# mainboard.net
KiCad netlist of a schematic drawn in EAGLE
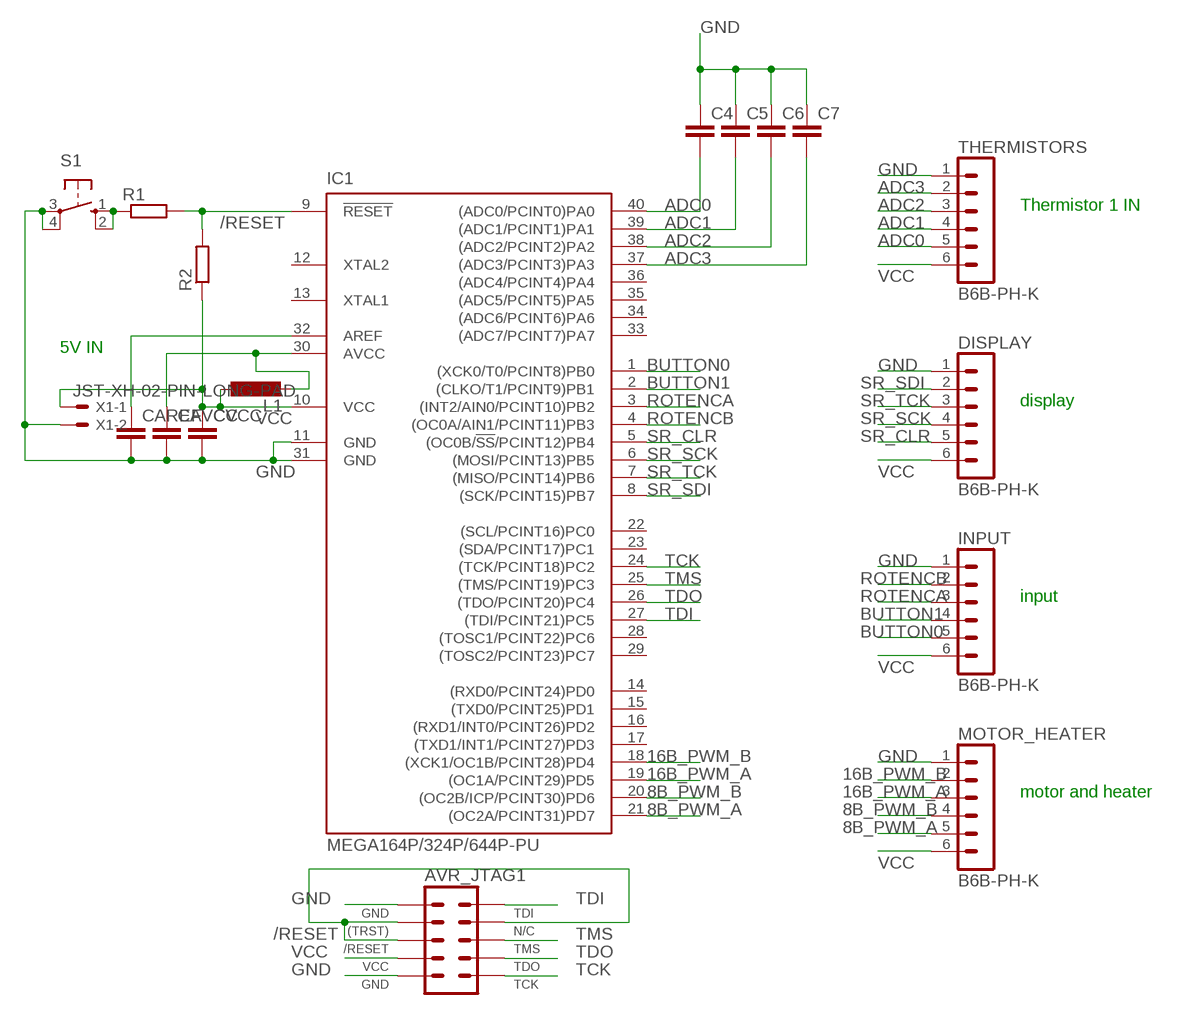
[diagram p0: schematic, sheet 1]

(export (version "E")
  (design (tool "Eeschema 10.0.6"))
  (components
    (comp (ref "AVR_JTAG1")
      (value "AVR_JTAG_2X5/IN")
      (footprint "eagle-import:AVR_JTAG_2X5")
      (libsource (lib "eagle-import") (part "AVR_JTAG_2X5/IN"))
    )
    (comp (ref "C4")
      (value "C-EU025-024X044")
      (footprint "eagle-import:C025-024X044")
      (libsource (lib "eagle-import") (part "C-EU025-024X044"))
    )
    (comp (ref "C5")
      (value "C-EU025-024X044")
      (footprint "eagle-import:C025-024X044")
      (libsource (lib "eagle-import") (part "C-EU025-024X044"))
    )
    (comp (ref "C6")
      (value "C-EU025-024X044")
      (footprint "eagle-import:C025-024X044")
      (libsource (lib "eagle-import") (part "C-EU025-024X044"))
    )
    (comp (ref "C7")
      (value "C-EU025-024X044")
      (footprint "eagle-import:C025-024X044")
      (libsource (lib "eagle-import") (part "C-EU025-024X044"))
    )
    (comp (ref "CAREF")
      (value "C-EU025-024X044")
      (footprint "eagle-import:C025-024X044")
      (libsource (lib "eagle-import") (part "C-EU025-024X044"))
    )
    (comp (ref "CAVCC")
      (value "C-EU025-024X044")
      (footprint "eagle-import:C025-024X044")
      (libsource (lib "eagle-import") (part "C-EU025-024X044"))
    )
    (comp (ref "CVCC")
      (value "C-EU025-024X044")
      (footprint "eagle-import:C025-024X044")
      (libsource (lib "eagle-import") (part "C-EU025-024X044"))
    )
    (comp (ref "DISPLAY")
      (value "B6B-PH-K")
      (footprint "eagle-import:B6B-PH-K")
      (libsource (lib "eagle-import") (part "B6B-PH-K"))
    )
    (comp (ref "IC1")
      (value "MEGA164P/324P/644P-PU")
      (footprint "eagle-import:DIL40")
      (libsource (lib "eagle-import") (part "MEGA164P/324P/644P-PU"))
    )
    (comp (ref "INPUT")
      (value "B6B-PH-K")
      (footprint "eagle-import:B6B-PH-K")
      (libsource (lib "eagle-import") (part "B6B-PH-K"))
    )
    (comp (ref "L1")
      (value "L-EU0207/10")
      (footprint "eagle-import:0207_10")
      (libsource (lib "eagle-import") (part "L-EU0207/10"))
    )
    (comp (ref "MOTOR_HEATER")
      (value "B6B-PH-K")
      (footprint "eagle-import:B6B-PH-K")
      (libsource (lib "eagle-import") (part "B6B-PH-K"))
    )
    (comp (ref "R1")
      (value "R-EU_0207/10")
      (footprint "eagle-import:0207_10")
      (libsource (lib "eagle-import") (part "R-EU_0207/10"))
    )
    (comp (ref "R2")
      (value "R-EU_0207/10")
      (footprint "eagle-import:0207_10")
      (libsource (lib "eagle-import") (part "R-EU_0207/10"))
    )
    (comp (ref "S1")
      (value "10-XX")
      (footprint "eagle-import:B3F-10XX")
      (libsource (lib "eagle-import") (part "10-XX"))
    )
    (comp (ref "THERMISTORS")
      (value "B6B-PH-K")
      (footprint "eagle-import:B6B-PH-K")
      (libsource (lib "eagle-import") (part "B6B-PH-K"))
    )
    (comp (ref "X1")
      (value "JST-XH-02-PIN-LONG-PAD")
      (footprint "eagle-import:JST-XH-02-PACKAGE-LONG-PAD")
      (libsource (lib "eagle-import") (part "JST-XH-02-PIN-LONG-PAD"))
    )
  )
  (nets
    (net (code "1") (name "/8B_PWM_A") (class "Default")
      (node (ref "IC1") (pin "21") (pinfunction "(OC2A/PCINT31)PD7_21") (pintype "bidirectional"))
      (node (ref "MOTOR_HEATER") (pin "5") (pinfunction "5_5") (pintype "passive"))
    )
    (net (code "2") (name "/8B_PWM_B") (class "Default")
      (node (ref "IC1") (pin "20") (pinfunction "(OC2B/ICP/PCINT30)PD6_20") (pintype "bidirectional"))
      (node (ref "MOTOR_HEATER") (pin "4") (pinfunction "4_4") (pintype "passive"))
    )
    (net (code "3") (name "/16B_PWM_A") (class "Default")
      (node (ref "IC1") (pin "19") (pinfunction "(OC1A/PCINT29)PD5_19") (pintype "bidirectional"))
      (node (ref "MOTOR_HEATER") (pin "3") (pinfunction "3_3") (pintype "passive"))
    )
    (net (code "4") (name "/16B_PWM_B") (class "Default")
      (node (ref "IC1") (pin "18") (pinfunction "(XCK1/OC1B/PCINT28)PD4_18") (pintype "bidirectional"))
      (node (ref "MOTOR_HEATER") (pin "2") (pinfunction "2_2") (pintype "passive"))
    )
    (net (code "5") (name "/ADC0") (class "Default")
      (node (ref "C4") (pin "2") (pinfunction "2_2") (pintype "passive"))
      (node (ref "IC1") (pin "40") (pinfunction "(ADC0/PCINT0)PA0_40") (pintype "bidirectional"))
      (node (ref "THERMISTORS") (pin "5") (pinfunction "5_5") (pintype "passive"))
    )
    (net (code "6") (name "/ADC1") (class "Default")
      (node (ref "C5") (pin "2") (pinfunction "2_2") (pintype "passive"))
      (node (ref "IC1") (pin "39") (pinfunction "(ADC1/PCINT1)PA1_39") (pintype "bidirectional"))
      (node (ref "THERMISTORS") (pin "4") (pinfunction "4_4") (pintype "passive"))
    )
    (net (code "7") (name "/ADC2") (class "Default")
      (node (ref "C6") (pin "2") (pinfunction "2_2") (pintype "passive"))
      (node (ref "IC1") (pin "38") (pinfunction "(ADC2/PCINT2)PA2_38") (pintype "bidirectional"))
      (node (ref "THERMISTORS") (pin "3") (pinfunction "3_3") (pintype "passive"))
    )
    (net (code "8") (name "/ADC3") (class "Default")
      (node (ref "C7") (pin "2") (pinfunction "2_2") (pintype "passive"))
      (node (ref "IC1") (pin "37") (pinfunction "(ADC3/PCINT3)PA3_37") (pintype "bidirectional"))
      (node (ref "THERMISTORS") (pin "2") (pinfunction "2_2") (pintype "passive"))
    )
    (net (code "9") (name "/BUTTON0") (class "Default")
      (node (ref "IC1") (pin "1") (pinfunction "(XCK0/T0/PCINT8)PB0_1") (pintype "bidirectional"))
      (node (ref "INPUT") (pin "5") (pinfunction "5_5") (pintype "passive"))
    )
    (net (code "10") (name "/BUTTON1") (class "Default")
      (node (ref "IC1") (pin "2") (pinfunction "(CLKO/T1/PCINT9)PB1_2") (pintype "bidirectional"))
      (node (ref "INPUT") (pin "4") (pinfunction "4_4") (pintype "passive"))
    )
    (net (code "11") (name "/GND") (class "Default")
      (node (ref "AVR_JTAG1") (pin "10") (pinfunction "GND2_10") (pintype "bidirectional"))
      (node (ref "AVR_JTAG1") (pin "2") (pinfunction "GND1_2") (pintype "bidirectional"))
      (node (ref "C4") (pin "1") (pinfunction "1_1") (pintype "passive"))
      (node (ref "C5") (pin "1") (pinfunction "1_1") (pintype "passive"))
      (node (ref "C6") (pin "1") (pinfunction "1_1") (pintype "passive"))
      (node (ref "C7") (pin "1") (pinfunction "1_1") (pintype "passive"))
      (node (ref "CAREF") (pin "2") (pinfunction "2_2") (pintype "passive"))
      (node (ref "CAVCC") (pin "2") (pinfunction "2_2") (pintype "passive"))
      (node (ref "CVCC") (pin "2") (pinfunction "2_2") (pintype "passive"))
      (node (ref "DISPLAY") (pin "1") (pinfunction "1_1") (pintype "passive"))
      (node (ref "IC1") (pin "11") (pinfunction "GND_11") (pintype "power_in"))
      (node (ref "IC1") (pin "31") (pinfunction "GND_31") (pintype "power_in"))
      (node (ref "INPUT") (pin "1") (pinfunction "1_1") (pintype "passive"))
      (node (ref "MOTOR_HEATER") (pin "1") (pinfunction "1_1") (pintype "passive"))
      (node (ref "S1") (pin "3") (pinfunction "P_3") (pintype "passive"))
      (node (ref "S1") (pin "4") (pinfunction "P1_4") (pintype "passive"))
      (node (ref "THERMISTORS") (pin "1") (pinfunction "1_1") (pintype "passive"))
      (node (ref "X1") (pin "2") (pinfunction "S_2") (pintype "passive"))
    )
    (net (code "12") (name "/ROTENCA") (class "Default")
      (node (ref "IC1") (pin "3") (pinfunction "(INT2/AIN0/PCINT10)PB2_3") (pintype "bidirectional"))
      (node (ref "INPUT") (pin "3") (pinfunction "3_3") (pintype "passive"))
    )
    (net (code "13") (name "/ROTENCB") (class "Default")
      (node (ref "IC1") (pin "4") (pinfunction "(OC0A/AIN1/PCINT11)PB3_4") (pintype "bidirectional"))
      (node (ref "INPUT") (pin "2") (pinfunction "2_2") (pintype "passive"))
    )
    (net (code "14") (name "/SR_CLR") (class "Default")
      (node (ref "DISPLAY") (pin "5") (pinfunction "5_5") (pintype "passive"))
      (node (ref "IC1") (pin "5") (pinfunction "(OC0B/~{SS}/PCINT12)PB4_5") (pintype "bidirectional"))
    )
    (net (code "15") (name "/SR_SCK") (class "Default")
      (node (ref "DISPLAY") (pin "4") (pinfunction "4_4") (pintype "passive"))
      (node (ref "IC1") (pin "6") (pinfunction "(MOSI/PCINT13)PB5_6") (pintype "bidirectional"))
    )
    (net (code "16") (name "/SR_SDI") (class "Default")
      (node (ref "DISPLAY") (pin "2") (pinfunction "2_2") (pintype "passive"))
      (node (ref "IC1") (pin "8") (pinfunction "(SCK/PCINT15)PB7_8") (pintype "bidirectional"))
    )
    (net (code "17") (name "/SR_TCK") (class "Default")
      (node (ref "DISPLAY") (pin "3") (pinfunction "3_3") (pintype "passive"))
      (node (ref "IC1") (pin "7") (pinfunction "(MISO/PCINT14)PB6_7") (pintype "bidirectional"))
    )
    (net (code "18") (name "/TCK") (class "Default")
      (node (ref "AVR_JTAG1") (pin "1") (pinfunction "TCK_1") (pintype "bidirectional"))
      (node (ref "IC1") (pin "24") (pinfunction "(TCK/PCINT18)PC2_24") (pintype "bidirectional"))
    )
    (net (code "19") (name "/TDI") (class "Default")
      (node (ref "AVR_JTAG1") (pin "9") (pinfunction "TDI_9") (pintype "bidirectional"))
      (node (ref "IC1") (pin "27") (pinfunction "(TDI/PCINT21)PC5_27") (pintype "bidirectional"))
    )
    (net (code "20") (name "/TDO") (class "Default")
      (node (ref "AVR_JTAG1") (pin "3") (pinfunction "TDO_3") (pintype "bidirectional"))
      (node (ref "IC1") (pin "26") (pinfunction "(TDO/PCINT20)PC4_26") (pintype "bidirectional"))
    )
    (net (code "21") (name "/TMS") (class "Default")
      (node (ref "AVR_JTAG1") (pin "5") (pinfunction "TMS_5") (pintype "bidirectional"))
      (node (ref "IC1") (pin "25") (pinfunction "(TMS/PCINT19)PC3_25") (pintype "bidirectional"))
    )
    (net (code "22") (name "/VCC") (class "Default")
      (node (ref "AVR_JTAG1") (pin "4") (pinfunction "VCC_4") (pintype "bidirectional"))
      (node (ref "CVCC") (pin "1") (pinfunction "1_1") (pintype "passive"))
      (node (ref "DISPLAY") (pin "6") (pinfunction "6_6") (pintype "passive"))
      (node (ref "IC1") (pin "10") (pinfunction "VCC_10") (pintype "power_in"))
      (node (ref "INPUT") (pin "6") (pinfunction "6_6") (pintype "passive"))
      (node (ref "L1") (pin "1") (pinfunction "1_1") (pintype "passive"))
      (node (ref "MOTOR_HEATER") (pin "6") (pinfunction "6_6") (pintype "passive"))
      (node (ref "R2") (pin "1") (pinfunction "1_1") (pintype "passive"))
      (node (ref "THERMISTORS") (pin "6") (pinfunction "6_6") (pintype "passive"))
      (node (ref "X1") (pin "1") (pinfunction "S_1") (pintype "passive"))
    )
    (net (code "23") (name "/{slash}RESET") (class "Default")
      (node (ref "AVR_JTAG1") (pin "6") (pinfunction "/RESET_6") (pintype "bidirectional"))
      (node (ref "AVR_JTAG1") (pin "7") (pinfunction "N/C_7") (pintype "bidirectional"))
      (node (ref "AVR_JTAG1") (pin "8") (pinfunction "(TRST)_8") (pintype "bidirectional"))
      (node (ref "IC1") (pin "9") (pinfunction "~{RESET}_9") (pintype "input"))
      (node (ref "R1") (pin "2") (pinfunction "2_2") (pintype "passive"))
      (node (ref "R2") (pin "2") (pinfunction "2_2") (pintype "passive"))
    )
    (net (code "24") (name "Net-(IC1-AREF)") (class "Default")
      (node (ref "CAREF") (pin "1") (pinfunction "1_1") (pintype "passive"))
      (node (ref "IC1") (pin "32") (pinfunction "AREF_32") (pintype "power_in"))
    )
    (net (code "25") (name "Net-(IC1-AVCC)") (class "Default")
      (node (ref "CAVCC") (pin "1") (pinfunction "1_1") (pintype "passive"))
      (node (ref "IC1") (pin "30") (pinfunction "AVCC_30") (pintype "power_in"))
      (node (ref "L1") (pin "2") (pinfunction "2_2") (pintype "passive"))
    )
    (net (code "26") (name "Net-(S1-S)") (class "Default")
      (node (ref "R1") (pin "1") (pinfunction "1_1") (pintype "passive"))
      (node (ref "S1") (pin "1") (pinfunction "S_1") (pintype "passive"))
      (node (ref "S1") (pin "2") (pinfunction "S1_2") (pintype "passive"))
    )
    (net (code "27") (name "unconnected-(IC1-(ADC4{slash}PCINT4)PA4-Pad36)") (class "Default")
      (node (ref "IC1") (pin "36") (pinfunction "(ADC4/PCINT4)PA4_36") (pintype "bidirectional"))
    )
    (net (code "28") (name "unconnected-(IC1-(ADC5{slash}PCINT5)PA5-Pad35)") (class "Default")
      (node (ref "IC1") (pin "35") (pinfunction "(ADC5/PCINT5)PA5_35") (pintype "bidirectional"))
    )
    (net (code "29") (name "unconnected-(IC1-(ADC6{slash}PCINT6)PA6-Pad34)") (class "Default")
      (node (ref "IC1") (pin "34") (pinfunction "(ADC6/PCINT6)PA6_34") (pintype "bidirectional"))
    )
    (net (code "30") (name "unconnected-(IC1-(ADC7{slash}PCINT7)PA7-Pad33)") (class "Default")
      (node (ref "IC1") (pin "33") (pinfunction "(ADC7/PCINT7)PA7_33") (pintype "bidirectional"))
    )
    (net (code "31") (name "unconnected-(IC1-(RXD0{slash}PCINT24)PD0-Pad14)") (class "Default")
      (node (ref "IC1") (pin "14") (pinfunction "(RXD0/PCINT24)PD0_14") (pintype "bidirectional"))
    )
    (net (code "32") (name "unconnected-(IC1-(RXD1{slash}INT0{slash}PCINT26)PD2-Pad16)") (class "Default")
      (node (ref "IC1") (pin "16") (pinfunction "(RXD1/INT0/PCINT26)PD2_16") (pintype "bidirectional"))
    )
    (net (code "33") (name "unconnected-(IC1-(SCL{slash}PCINT16)PC0-Pad22)") (class "Default")
      (node (ref "IC1") (pin "22") (pinfunction "(SCL/PCINT16)PC0_22") (pintype "bidirectional"))
    )
    (net (code "34") (name "unconnected-(IC1-(SDA{slash}PCINT17)PC1-Pad23)") (class "Default")
      (node (ref "IC1") (pin "23") (pinfunction "(SDA/PCINT17)PC1_23") (pintype "bidirectional"))
    )
    (net (code "35") (name "unconnected-(IC1-(TOSC1{slash}PCINT22)PC6-Pad28)") (class "Default")
      (node (ref "IC1") (pin "28") (pinfunction "(TOSC1/PCINT22)PC6_28") (pintype "bidirectional"))
    )
    (net (code "36") (name "unconnected-(IC1-(TOSC2{slash}PCINT23)PC7-Pad29)") (class "Default")
      (node (ref "IC1") (pin "29") (pinfunction "(TOSC2/PCINT23)PC7_29") (pintype "bidirectional"))
    )
    (net (code "37") (name "unconnected-(IC1-(TXD0{slash}PCINT25)PD1-Pad15)") (class "Default")
      (node (ref "IC1") (pin "15") (pinfunction "(TXD0/PCINT25)PD1_15") (pintype "bidirectional"))
    )
    (net (code "38") (name "unconnected-(IC1-(TXD1{slash}INT1{slash}PCINT27)PD3-Pad17)") (class "Default")
      (node (ref "IC1") (pin "17") (pinfunction "(TXD1/INT1/PCINT27)PD3_17") (pintype "bidirectional"))
    )
    (net (code "39") (name "unconnected-(IC1-XTAL1-Pad13)") (class "Default")
      (node (ref "IC1") (pin "13") (pinfunction "XTAL1_13") (pintype "input"))
    )
    (net (code "40") (name "unconnected-(IC1-XTAL2-Pad12)") (class "Default")
      (node (ref "IC1") (pin "12") (pinfunction "XTAL2_12") (pintype "output"))
    )
  )
)
